# pc_healthypi_move_sensor_dual.net
KiCad netlist of a schematic drawn in EAGLE
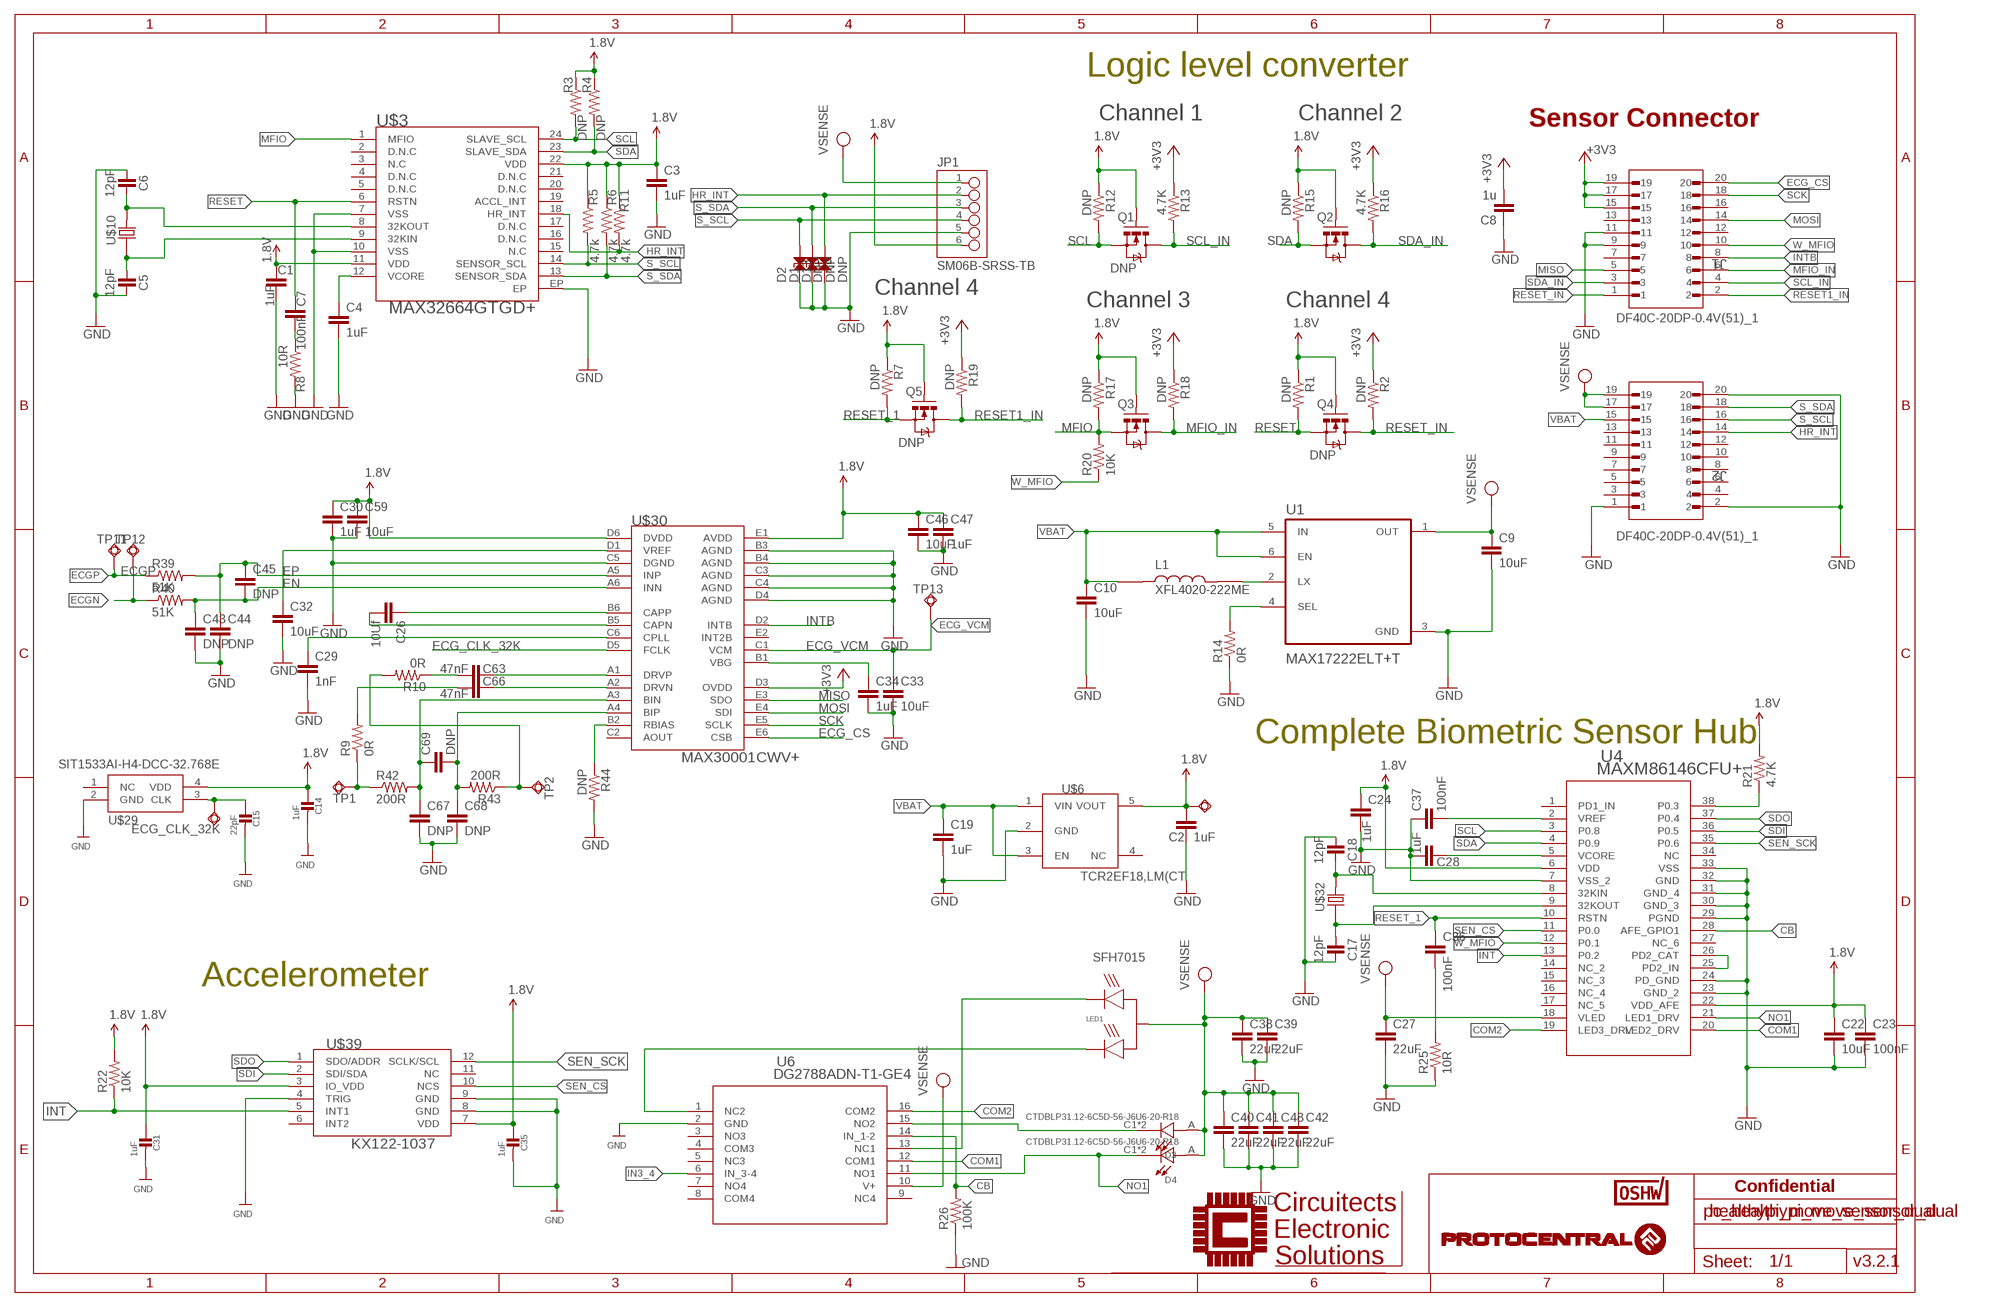
[diagram p0: schematic, sheet 1]

(export (version "E")
  (design (tool "Eeschema 10.0.6"))
  (components
    (comp (ref "C1")
      (value "1uF")
      (footprint "eagle-import:C0402")
      (libsource (lib "eagle-import") (part "C-EUC0402"))
    )
    (comp (ref "C2")
      (value "1uF")
      (footprint "eagle-import:C0402")
      (libsource (lib "eagle-import") (part "C-EUC0402"))
    )
    (comp (ref "C3")
      (value "1uF")
      (footprint "eagle-import:C0402")
      (libsource (lib "eagle-import") (part "C-EUC0402"))
    )
    (comp (ref "C4")
      (value "1uF")
      (footprint "eagle-import:C0402")
      (libsource (lib "eagle-import") (part "C-EUC0402"))
    )
    (comp (ref "C5")
      (value "12pF")
      (footprint "eagle-import:C0402")
      (libsource (lib "eagle-import") (part "CAPACITORS-0402"))
    )
    (comp (ref "C6")
      (value "12pF")
      (footprint "eagle-import:C0402")
      (libsource (lib "eagle-import") (part "CAPACITORS-0402"))
    )
    (comp (ref "C7")
      (value "100nF")
      (footprint "eagle-import:C0402")
      (libsource (lib "eagle-import") (part "C-EUC0402"))
    )
    (comp (ref "C8")
      (value "1u")
      (footprint "eagle-import:C0402")
      (libsource (lib "eagle-import") (part "C-EUC0402"))
    )
    (comp (ref "C9")
      (value "10uF")
      (footprint "eagle-import:C0402")
      (libsource (lib "eagle-import") (part "C-EUC0402"))
    )
    (comp (ref "C10")
      (value "10uF")
      (footprint "eagle-import:C0402")
      (libsource (lib "eagle-import") (part "C-EUC0402"))
    )
    (comp (ref "C14")
      (value "1uF")
      (footprint "eagle-import:0402")
      (libsource (lib "eagle-import") (part "CAP_CERAMIC0402"))
    )
    (comp (ref "C15")
      (value "22pF")
      (footprint "eagle-import:0402")
      (libsource (lib "eagle-import") (part "CAP_CERAMIC0402"))
    )
    (comp (ref "C17")
      (value "12pF")
      (footprint "eagle-import:C0402")
      (libsource (lib "eagle-import") (part "CAPACITORS-0402"))
    )
    (comp (ref "C18")
      (value "12pF")
      (footprint "eagle-import:C0402")
      (libsource (lib "eagle-import") (part "CAPACITORS-0402"))
    )
    (comp (ref "C19")
      (value "1uF")
      (footprint "eagle-import:C0402")
      (libsource (lib "eagle-import") (part "C-EUC0402"))
    )
    (comp (ref "C22")
      (value "10uF")
      (footprint "eagle-import:C0402")
      (libsource (lib "eagle-import") (part "C-EUC0402"))
    )
    (comp (ref "C23")
      (value "100nF")
      (footprint "eagle-import:C0402")
      (libsource (lib "eagle-import") (part "C-EUC0402"))
    )
    (comp (ref "C24")
      (value "1uF")
      (footprint "eagle-import:C0402")
      (libsource (lib "eagle-import") (part "C-EUC0402"))
    )
    (comp (ref "C26")
      (value "10Uf")
      (footprint "eagle-import:C0402")
      (libsource (lib "eagle-import") (part "C-EUC0402"))
    )
    (comp (ref "C27")
      (value "22uF")
      (footprint "eagle-import:C0805")
      (libsource (lib "eagle-import") (part "C-EUC0805"))
    )
    (comp (ref "C28")
      (value "1uF")
      (footprint "eagle-import:C0402")
      (libsource (lib "eagle-import") (part "C-EUC0402"))
    )
    (comp (ref "C29")
      (value "1nF")
      (footprint "eagle-import:C0402")
      (libsource (lib "eagle-import") (part "C-EUC0402"))
    )
    (comp (ref "C30")
      (value "1uF")
      (footprint "eagle-import:C0402")
      (libsource (lib "eagle-import") (part "C-EUC0402"))
    )
    (comp (ref "C31")
      (value "1uF")
      (footprint "eagle-import:0402")
      (libsource (lib "eagle-import") (part "CAP_CERAMIC0402"))
    )
    (comp (ref "C32")
      (value "10uF")
      (footprint "eagle-import:C0402")
      (libsource (lib "eagle-import") (part "C-EUC0402"))
    )
    (comp (ref "C33")
      (value "10uF")
      (footprint "eagle-import:C0402")
      (libsource (lib "eagle-import") (part "C-EUC0402"))
    )
    (comp (ref "C34")
      (value "1uF")
      (footprint "eagle-import:C0402")
      (libsource (lib "eagle-import") (part "C-EUC0402"))
    )
    (comp (ref "C35")
      (value "1uF")
      (footprint "eagle-import:0402")
      (libsource (lib "eagle-import") (part "CAP_CERAMIC0402"))
    )
    (comp (ref "C36")
      (value "100nF")
      (footprint "eagle-import:C0402")
      (libsource (lib "eagle-import") (part "C-EUC0402"))
    )
    (comp (ref "C37")
      (value "100nF")
      (footprint "eagle-import:C0402")
      (libsource (lib "eagle-import") (part "C-EUC0402"))
    )
    (comp (ref "C38")
      (value "22uF")
      (footprint "eagle-import:C0805")
      (libsource (lib "eagle-import") (part "C-EUC0805"))
    )
    (comp (ref "C39")
      (value "22uF")
      (footprint "eagle-import:C0805")
      (libsource (lib "eagle-import") (part "C-EUC0805"))
    )
    (comp (ref "C40")
      (value "22uF")
      (footprint "eagle-import:C0805")
      (libsource (lib "eagle-import") (part "C-EUC0805"))
    )
    (comp (ref "C41")
      (value "22uF")
      (footprint "eagle-import:C0805")
      (libsource (lib "eagle-import") (part "C-EUC0805"))
    )
    (comp (ref "C42")
      (value "22uF")
      (footprint "eagle-import:C0805")
      (libsource (lib "eagle-import") (part "C-EUC0805"))
    )
    (comp (ref "C43")
      (value "DNP")
      (footprint "eagle-import:C0402")
      (libsource (lib "eagle-import") (part "C-EUC0402"))
    )
    (comp (ref "C44")
      (value "DNP")
      (footprint "eagle-import:C0402")
      (libsource (lib "eagle-import") (part "C-EUC0402"))
    )
    (comp (ref "C45")
      (value "DNP")
      (footprint "eagle-import:C0402")
      (libsource (lib "eagle-import") (part "C-EUC0402"))
    )
    (comp (ref "C46")
      (value "10uF")
      (footprint "eagle-import:C0402")
      (libsource (lib "eagle-import") (part "C-EUC0402"))
    )
    (comp (ref "C47")
      (value "1uF")
      (footprint "eagle-import:C0402")
      (libsource (lib "eagle-import") (part "C-EUC0402"))
    )
    (comp (ref "C48")
      (value "22uF")
      (footprint "eagle-import:C0805")
      (libsource (lib "eagle-import") (part "C-EUC0805"))
    )
    (comp (ref "C59")
      (value "10uF")
      (footprint "eagle-import:C0402")
      (libsource (lib "eagle-import") (part "C-EUC0402"))
    )
    (comp (ref "C63")
      (value "47nF")
      (footprint "eagle-import:C0402")
      (libsource (lib "eagle-import") (part "C-EUC0402"))
    )
    (comp (ref "C66")
      (value "47nF")
      (footprint "eagle-import:C0402")
      (libsource (lib "eagle-import") (part "C-EUC0402"))
    )
    (comp (ref "C67")
      (value "DNP")
      (footprint "eagle-import:C0402")
      (libsource (lib "eagle-import") (part "C-EUC0402"))
    )
    (comp (ref "C68")
      (value "DNP")
      (footprint "eagle-import:C0402")
      (libsource (lib "eagle-import") (part "C-EUC0402"))
    )
    (comp (ref "C69")
      (value "DNP")
      (footprint "eagle-import:C0402")
      (libsource (lib "eagle-import") (part "C-EUC0402"))
    )
    (comp (ref "D1")
      (value "DNP")
      (footprint "eagle-import:0402")
      (fields
        (field (name "DIGIKEY_PART") "PESD0402-140CT-ND")
        (field (name "MOUSE_PART") "650-PESD0402-140")
      )
      (libsource (lib "eagle-import") (part "PESD0402-0402"))
    )
    (comp (ref "D2")
      (value "DNP")
      (footprint "eagle-import:0402")
      (fields
        (field (name "DIGIKEY_PART") "PESD0402-140CT-ND")
        (field (name "MOUSE_PART") "650-PESD0402-140")
      )
      (libsource (lib "eagle-import") (part "PESD0402-0402"))
    )
    (comp (ref "D3")
      (value "CTDBLP31.12-6C5D-56-J6U6-20-R18")
      (footprint "eagle-import:LED_CTDBLP31.12-6C5D-56-J6U6-20-R18")
      (fields
        (field (name "MF") "OSRAM Opto Semiconductors")
        (field (name "MP") "CT DBLP31.12-6C5D-56-J6U6-20-R18")
      )
      (libsource (lib "eagle-import") (part "CTDBLP31.12-6C5D-56-J6U6-20-R18"))
    )
    (comp (ref "D4")
      (value "CTDBLP31.12-6C5D-56-J6U6-20-R18")
      (footprint "eagle-import:LED_CTDBLP31.12-6C5D-56-J6U6-20-R18")
      (fields
        (field (name "MF") "OSRAM Opto Semiconductors")
        (field (name "MP") "CT DBLP31.12-6C5D-56-J6U6-20-R18")
      )
      (libsource (lib "eagle-import") (part "CTDBLP31.12-6C5D-56-J6U6-20-R18"))
    )
    (comp (ref "D13")
      (value "DNP")
      (footprint "eagle-import:0402")
      (fields
        (field (name "DIGIKEY_PART") "PESD0402-140CT-ND")
        (field (name "MOUSE_PART") "650-PESD0402-140")
      )
      (libsource (lib "eagle-import") (part "PESD0402-0402"))
    )
    (comp (ref "J1")
      (value "DF40C-20DP-0.4V(51)_1")
      (footprint "eagle-import:HRS_DF40C-20DP-0.4V(51)")
      (fields (field (name "MANUFACTURER") "Hirose Electric"))
      (libsource (lib "eagle-import") (part "DF40C-20DP-0.4V(51)_1"))
    )
    (comp (ref "J2")
      (value "DF40C-20DP-0.4V(51)_1")
      (footprint "eagle-import:HRS_DF40C-20DP-0.4V(51)")
      (fields (field (name "MANUFACTURER") "Hirose Electric"))
      (libsource (lib "eagle-import") (part "DF40C-20DP-0.4V(51)_1"))
    )
    (comp (ref "JP1")
      (value "SM06B-SRSS-TB")
      (footprint "eagle-import:SM06B-SRSS-TB")
      (fields (field (name "MF") "JST Sales"))
      (libsource (lib "eagle-import") (part "SM06B-SRSS-TB"))
    )
    (comp (ref "L1")
      (value "XFL4020-222ME")
      (footprint "eagle-import:IND_XFL4020-222ME")
      (fields (field (name "MF") "Coilcraft"))
      (libsource (lib "eagle-import") (part "XFL4020-222ME"))
    )
    (comp (ref "LED1")
      (value "SFH7015")
      (footprint "eagle-import:SFH7015")
      (fields (field (name "MF") "OSRAM Opto Semiconductors") (field (name "MP") "SFH 7015"))
      (libsource (lib "eagle-import") (part "SFH7015"))
    )
    (comp (ref "Q1")
      (value "DNP")
      (footprint "eagle-import:SOT23-3")
      (libsource (lib "eagle-import") (part "MOSFET-NCHANNELSMD"))
    )
    (comp (ref "Q2")
      (value "DNP")
      (footprint "eagle-import:SOT23-3")
      (libsource (lib "eagle-import") (part "MOSFET-NCHANNELSMD"))
    )
    (comp (ref "Q3")
      (value "DNP")
      (footprint "eagle-import:SOT23-3")
      (libsource (lib "eagle-import") (part "MOSFET-NCHANNELSMD"))
    )
    (comp (ref "Q4")
      (value "DNP")
      (footprint "eagle-import:SOT23-3")
      (libsource (lib "eagle-import") (part "MOSFET-NCHANNELSMD"))
    )
    (comp (ref "Q5")
      (value "DNP")
      (footprint "eagle-import:SOT23-3")
      (libsource (lib "eagle-import") (part "MOSFET-NCHANNELSMD"))
    )
    (comp (ref "R1")
      (value "DNP")
      (footprint "eagle-import:0402-RES")
      (libsource (lib "eagle-import") (part "RESISTOR0402-RES"))
    )
    (comp (ref "R2")
      (value "DNP")
      (footprint "eagle-import:0402-RES")
      (libsource (lib "eagle-import") (part "RESISTOR0402-RES"))
    )
    (comp (ref "R3")
      (value "DNP")
      (footprint "eagle-import:0402-RES")
      (libsource (lib "eagle-import") (part "RESISTOR0402-RES"))
    )
    (comp (ref "R4")
      (value "DNP")
      (footprint "eagle-import:0402-RES")
      (libsource (lib "eagle-import") (part "RESISTOR0402-RES"))
    )
    (comp (ref "R5")
      (value "4.7k")
      (footprint "eagle-import:0402-RES")
      (libsource (lib "eagle-import") (part "RESISTOR0402-RES"))
    )
    (comp (ref "R6")
      (value "4.7k")
      (footprint "eagle-import:0402-RES")
      (libsource (lib "eagle-import") (part "RESISTOR0402-RES"))
    )
    (comp (ref "R7")
      (value "DNP")
      (footprint "eagle-import:0402-RES")
      (libsource (lib "eagle-import") (part "RESISTOR0402-RES"))
    )
    (comp (ref "R8")
      (value "10R")
      (footprint "eagle-import:0402-RES")
      (libsource (lib "eagle-import") (part "RESISTOR0402-RES"))
    )
    (comp (ref "R9")
      (value "0R")
      (footprint "eagle-import:0402-RES")
      (libsource (lib "eagle-import") (part "RESISTOR0402-RES"))
    )
    (comp (ref "R10")
      (value "0R")
      (footprint "eagle-import:0402-RES")
      (libsource (lib "eagle-import") (part "RESISTOR0402-RES"))
    )
    (comp (ref "R11")
      (value "4.7k")
      (footprint "eagle-import:0402-RES")
      (libsource (lib "eagle-import") (part "RESISTOR0402-RES"))
    )
    (comp (ref "R12")
      (value "DNP")
      (footprint "eagle-import:0402-RES")
      (libsource (lib "eagle-import") (part "RESISTOR0402-RES"))
    )
    (comp (ref "R13")
      (value "4.7K")
      (footprint "eagle-import:0402-RES")
      (libsource (lib "eagle-import") (part "RESISTOR0402-RES"))
    )
    (comp (ref "R14")
      (value "0R")
      (footprint "eagle-import:R0402")
      (libsource (lib "eagle-import") (part "R-US_R0402"))
    )
    (comp (ref "R15")
      (value "DNP")
      (footprint "eagle-import:0402-RES")
      (libsource (lib "eagle-import") (part "RESISTOR0402-RES"))
    )
    (comp (ref "R16")
      (value "4.7K")
      (footprint "eagle-import:0402-RES")
      (libsource (lib "eagle-import") (part "RESISTOR0402-RES"))
    )
    (comp (ref "R17")
      (value "DNP")
      (footprint "eagle-import:0402-RES")
      (libsource (lib "eagle-import") (part "RESISTOR0402-RES"))
    )
    (comp (ref "R18")
      (value "DNP")
      (footprint "eagle-import:0402-RES")
      (libsource (lib "eagle-import") (part "RESISTOR0402-RES"))
    )
    (comp (ref "R19")
      (value "DNP")
      (footprint "eagle-import:0402-RES")
      (libsource (lib "eagle-import") (part "RESISTOR0402-RES"))
    )
    (comp (ref "R20")
      (value "10K")
      (footprint "eagle-import:0402-RES")
      (libsource (lib "eagle-import") (part "RESISTOR0402-RES"))
    )
    (comp (ref "R21")
      (value "4.7K")
      (footprint "eagle-import:R0402")
      (libsource (lib "eagle-import") (part "R-US_R0402"))
    )
    (comp (ref "R22")
      (value "10K")
      (footprint "eagle-import:0402-RES")
      (libsource (lib "eagle-import") (part "RESISTOR0402-RES"))
    )
    (comp (ref "R25")
      (value "10R")
      (footprint "eagle-import:R0402")
      (libsource (lib "eagle-import") (part "R-US_R0402"))
    )
    (comp (ref "R26")
      (value "100K")
      (footprint "eagle-import:R0402")
      (libsource (lib "eagle-import") (part "R-US_R0402"))
    )
    (comp (ref "R39")
      (value "51K")
      (footprint "eagle-import:0402-RES")
      (libsource (lib "eagle-import") (part "RESISTOR0402-RES"))
    )
    (comp (ref "R40")
      (value "51K")
      (footprint "eagle-import:0402-RES")
      (libsource (lib "eagle-import") (part "RESISTOR0402-RES"))
    )
    (comp (ref "R42")
      (value "200R")
      (footprint "eagle-import:0402-RES")
      (libsource (lib "eagle-import") (part "RESISTOR0402-RES"))
    )
    (comp (ref "R43")
      (value "200R")
      (footprint "eagle-import:0402-RES")
      (libsource (lib "eagle-import") (part "RESISTOR0402-RES"))
    )
    (comp (ref "R44")
      (value "DNP")
      (footprint "eagle-import:0402-RES")
      (libsource (lib "eagle-import") (part "RESISTOR0402-RES"))
    )
    (comp (ref "SWIO1")
      (value "TPSQTP11R")
      (footprint "eagle-import:TP11R")
      (libsource (lib "eagle-import") (part "TPSQTP11R"))
    )
    (comp (ref "SWIO5")
      (value "TPSQTP11R")
      (footprint "eagle-import:TP11R")
      (libsource (lib "eagle-import") (part "TPSQTP11R"))
    )
    (comp (ref "TP1")
      (value "TPSQTP20SQ")
      (footprint "eagle-import:TP20SQ")
      (libsource (lib "eagle-import") (part "TPSQTP20SQ"))
    )
    (comp (ref "TP2")
      (value "TPSQTP20SQ")
      (footprint "eagle-import:TP20SQ")
      (libsource (lib "eagle-import") (part "TPSQTP20SQ"))
    )
    (comp (ref "TP11")
      (value "TPSQTP20SQ")
      (footprint "eagle-import:TP20SQ")
      (libsource (lib "eagle-import") (part "TPSQTP20SQ"))
    )
    (comp (ref "TP12")
      (value "TPSQTP20SQ")
      (footprint "eagle-import:TP20SQ")
      (libsource (lib "eagle-import") (part "TPSQTP20SQ"))
    )
    (comp (ref "TP13")
      (value "TPSQTP20SQ")
      (footprint "eagle-import:TP20SQ")
      (libsource (lib "eagle-import") (part "TPSQTP20SQ"))
    )
    (comp (ref "U$3")
      (value "MAX32664GTGD+")
      (footprint "eagle-import:TQFN-24L")
      (libsource (lib "eagle-import") (part "MAX32664GTGA+"))
    )
    (comp (ref "U$6")
      (value "TCR2EF18,LM(CT")
      (footprint "eagle-import:SOT95P285X140-5N")
      (libsource (lib "eagle-import") (part "AP7354D-18W5-7"))
    )
    (comp (ref "U$10")
      (value "520-327-12.5-34B(32.768KHZ)")
      (footprint "eagle-import:ECX-31B")
      (libsource (lib "eagle-import") (part "ECS-X-34B"))
    )
    (comp (ref "U$29")
      (value "SIT1533AI-H4-DCC-32.768E")
      (footprint "eagle-import:SIT1533")
      (libsource (lib "eagle-import") (part "SIT1533AI-H4-DCC-32.768E"))
    )
    (comp (ref "U$30")
      (value "MAX30001CWV+")
      (footprint "eagle-import:30WLP")
      (libsource (lib "eagle-import") (part "MAX30001CWV+"))
    )
    (comp (ref "U$32")
      (value "520-327-12.5-34B(32.768KHZ)")
      (footprint "eagle-import:ECX-31B")
      (libsource (lib "eagle-import") (part "ECS-X-34B"))
    )
    (comp (ref "U$39")
      (value "KX122-1037")
      (footprint "eagle-import:KIONIX_KXTJ3-1057")
      (libsource (lib "eagle-import") (part "KX122-1037"))
    )
    (comp (ref "U$48")
      (value "CERT-SMALL")
      (footprint "eagle-import:CERT-SMALL-SILK")
      (libsource (lib "eagle-import") (part "CERT-SMALL"))
    )
    (comp (ref "U1")
      (value "MAX17222ELT+T")
      (footprint "eagle-import:SON65P200X200X80-6N")
      (fields (field (name "MF") "Analog Devices"))
      (libsource (lib "eagle-import") (part "MAX17222ELT+T"))
    )
    (comp (ref "U4")
      (value "MAXM86146CFU+")
      (footprint "eagle-import:21-100323A_90-100112A_MXM")
      (fields (field (name "COPYRIGHT") "Copyright (C) 2023 Ultra Librarian. All rights reserved."))
      (libsource (lib "eagle-import") (part "MAXM86146CFU+"))
    )
    (comp (ref "U6")
      (value "DG2788ADN-T1-GE4")
      (footprint "eagle-import:MINIQFN-16_VIS")
      (fields (field (name "COPYRIGHT") "Copyright (C) 2023 Ultra Librarian. All rights reserved."))
      (libsource (lib "eagle-import") (part "DG2788ADN-T1-GE4"))
    )
  )
  (nets
    (net (code "1") (name "+3V3") (class "Default")
      (node (ref "C8") (pin "2") (pinfunction "2_2") (pintype "passive"))
      (node (ref "J1") (pin "15") (pinfunction "15_15") (pintype "passive"))
      (node (ref "J1") (pin "17") (pinfunction "17_17") (pintype "passive"))
      (node (ref "J1") (pin "19") (pinfunction "19_19") (pintype "passive"))
      (node (ref "R13") (pin "1") (pinfunction "1_1") (pintype "passive"))
      (node (ref "R16") (pin "1") (pinfunction "1_1") (pintype "passive"))
      (node (ref "R18") (pin "1") (pinfunction "1_1") (pintype "passive"))
      (node (ref "R19") (pin "1") (pinfunction "1_1") (pintype "passive"))
      (node (ref "R2") (pin "1") (pinfunction "1_1") (pintype "passive"))
      (node (ref "U$30") (pin "D3") (pinfunction "OVDD_D3") (pintype "bidirectional"))
    )
    (net (code "2") (name "/ECG_CLK_32K") (class "Default")
      (node (ref "C15") (pin "1") (pinfunction "P$1_1") (pintype "passive"))
      (node (ref "SWIO1") (pin "TP") (pinfunction "TP_TP") (pintype "input"))
      (node (ref "U$29") (pin "3") (pinfunction "CLK_3") (pintype "bidirectional"))
      (node (ref "U$30") (pin "D5") (pinfunction "FCLK_D5") (pintype "bidirectional"))
    )
    (net (code "3") (name "/EN") (class "Default")
      (node (ref "C43") (pin "1") (pinfunction "1_1") (pintype "passive"))
      (node (ref "C45") (pin "2") (pinfunction "2_2") (pintype "passive"))
      (node (ref "R40") (pin "2") (pinfunction "2_2") (pintype "passive"))
      (node (ref "U$30") (pin "A6") (pinfunction "INN_A6") (pintype "bidirectional"))
    )
    (net (code "4") (name "/EP") (class "Default")
      (node (ref "C44") (pin "1") (pinfunction "1_1") (pintype "passive"))
      (node (ref "C45") (pin "1") (pinfunction "1_1") (pintype "passive"))
      (node (ref "R39") (pin "2") (pinfunction "2_2") (pintype "passive"))
      (node (ref "U$30") (pin "A5") (pinfunction "INP_A5") (pintype "bidirectional"))
    )
    (net (code "5") (name "1.8V") (class "Default")
      (node (ref "C1") (pin "1") (pinfunction "1_1") (pintype "passive"))
      (node (ref "C14") (pin "1") (pinfunction "P$1_1") (pintype "passive"))
      (node (ref "C2") (pin "1") (pinfunction "1_1") (pintype "passive"))
      (node (ref "C22") (pin "1") (pinfunction "1_1") (pintype "passive"))
      (node (ref "C23") (pin "1") (pinfunction "1_1") (pintype "passive"))
      (node (ref "C24") (pin "1") (pinfunction "1_1") (pintype "passive"))
      (node (ref "C3") (pin "1") (pinfunction "1_1") (pintype "passive"))
      (node (ref "C30") (pin "1") (pinfunction "1_1") (pintype "passive"))
      (node (ref "C31") (pin "1") (pinfunction "P$1_1") (pintype "passive"))
      (node (ref "C35") (pin "1") (pinfunction "P$1_1") (pintype "passive"))
      (node (ref "C46") (pin "1") (pinfunction "1_1") (pintype "passive"))
      (node (ref "C47") (pin "1") (pinfunction "1_1") (pintype "passive"))
      (node (ref "C59") (pin "1") (pinfunction "1_1") (pintype "passive"))
      (node (ref "JP1") (pin "6") (pinfunction "P$6_6") (pintype "bidirectional"))
      (node (ref "Q1") (pin "1") (pinfunction "G_1") (pintype "passive"))
      (node (ref "Q2") (pin "1") (pinfunction "G_1") (pintype "passive"))
      (node (ref "Q3") (pin "1") (pinfunction "G_1") (pintype "passive"))
      (node (ref "Q4") (pin "1") (pinfunction "G_1") (pintype "passive"))
      (node (ref "Q5") (pin "1") (pinfunction "G_1") (pintype "passive"))
      (node (ref "R1") (pin "1") (pinfunction "1_1") (pintype "passive"))
      (node (ref "R11") (pin "1") (pinfunction "1_1") (pintype "passive"))
      (node (ref "R12") (pin "1") (pinfunction "1_1") (pintype "passive"))
      (node (ref "R15") (pin "1") (pinfunction "1_1") (pintype "passive"))
      (node (ref "R17") (pin "1") (pinfunction "1_1") (pintype "passive"))
      (node (ref "R21") (pin "2") (pinfunction "2_2") (pintype "passive"))
      (node (ref "R22") (pin "2") (pinfunction "2_2") (pintype "passive"))
      (node (ref "R3") (pin "1") (pinfunction "1_1") (pintype "passive"))
      (node (ref "R4") (pin "1") (pinfunction "1_1") (pintype "passive"))
      (node (ref "R5") (pin "1") (pinfunction "1_1") (pintype "passive"))
      (node (ref "R6") (pin "1") (pinfunction "1_1") (pintype "passive"))
      (node (ref "R7") (pin "1") (pinfunction "1_1") (pintype "passive"))
      (node (ref "SWIO5") (pin "TP") (pinfunction "TP_TP") (pintype "input"))
      (node (ref "U$29") (pin "4") (pinfunction "VDD_4") (pintype "bidirectional"))
      (node (ref "U$3") (pin "11") (pinfunction "VDD_11") (pintype "bidirectional"))
      (node (ref "U$3") (pin "22") (pinfunction "VDD_22") (pintype "bidirectional"))
      (node (ref "U$30") (pin "D6") (pinfunction "DVDD_D6") (pintype "bidirectional"))
      (node (ref "U$30") (pin "E1") (pinfunction "AVDD_E1") (pintype "bidirectional"))
      (node (ref "U$39") (pin "3") (pinfunction "IO_VDD_3") (pintype "bidirectional"))
      (node (ref "U$39") (pin "7") (pinfunction "VDD_7") (pintype "bidirectional"))
      (node (ref "U$6") (pin "5") (pinfunction "VOUT_5") (pintype "bidirectional"))
      (node (ref "U4") (pin "22") (pinfunction "VDD_AFE_22") (pintype "input"))
      (node (ref "U4") (pin "6") (pinfunction "VDD_6") (pintype "power_in"))
    )
    (net (code "6") (name "CB") (class "Default")
      (node (ref "R26") (pin "2") (pinfunction "2_2") (pintype "passive"))
      (node (ref "U4") (pin "28") (pinfunction "AFE_GPIO1_28") (pintype "bidirectional"))
      (node (ref "U6") (pin "14") (pinfunction "IN_1-2_14") (pintype "bidirectional"))
    )
    (net (code "7") (name "COM1") (class "Default")
      (node (ref "U4") (pin "20") (pinfunction "LED2_DRV_20") (pintype "output"))
      (node (ref "U6") (pin "12") (pinfunction "COM1_12") (pintype "bidirectional"))
    )
    (net (code "8") (name "COM2") (class "Default")
      (node (ref "U4") (pin "19") (pinfunction "LED3_DRV_19") (pintype "output"))
      (node (ref "U6") (pin "16") (pinfunction "COM2_16") (pintype "bidirectional"))
    )
    (net (code "9") (name "ECGN") (class "Default")
      (node (ref "R40") (pin "1") (pinfunction "1_1") (pintype "passive"))
      (node (ref "TP12") (pin "TP") (pinfunction "TP_TP") (pintype "input"))
    )
    (net (code "10") (name "ECGP") (class "Default")
      (node (ref "R39") (pin "1") (pinfunction "1_1") (pintype "passive"))
      (node (ref "TP11") (pin "TP") (pinfunction "TP_TP") (pintype "input"))
    )
    (net (code "11") (name "ECG_CS") (class "Default")
      (node (ref "J1") (pin "20") (pinfunction "20_20") (pintype "passive"))
      (node (ref "U$30") (pin "E6") (pinfunction "CSB_E6") (pintype "bidirectional"))
    )
    (net (code "12") (name "ECG_VCM") (class "Default")
      (node (ref "C33") (pin "1") (pinfunction "1_1") (pintype "passive"))
      (node (ref "TP13") (pin "TP") (pinfunction "TP_TP") (pintype "input"))
      (node (ref "U$30") (pin "C1") (pinfunction "VCM_C1") (pintype "bidirectional"))
    )
    (net (code "13") (name "GND") (class "Default")
      (node (ref "C1") (pin "2") (pinfunction "2_2") (pintype "passive"))
      (node (ref "C10") (pin "2") (pinfunction "2_2") (pintype "passive"))
      (node (ref "C14") (pin "2") (pinfunction "P$2_2") (pintype "passive"))
      (node (ref "C15") (pin "2") (pinfunction "P$2_2") (pintype "passive"))
      (node (ref "C17") (pin "2") (pinfunction "2_2") (pintype "passive"))
      (node (ref "C18") (pin "1") (pinfunction "1_1") (pintype "passive"))
      (node (ref "C19") (pin "2") (pinfunction "2_2") (pintype "passive"))
      (node (ref "C2") (pin "2") (pinfunction "2_2") (pintype "passive"))
      (node (ref "C22") (pin "2") (pinfunction "2_2") (pintype "passive"))
      (node (ref "C23") (pin "2") (pinfunction "2_2") (pintype "passive"))
      (node (ref "C24") (pin "2") (pinfunction "2_2") (pintype "passive"))
      (node (ref "C27") (pin "2") (pinfunction "2_2") (pintype "passive"))
      (node (ref "C28") (pin "2") (pinfunction "2_2") (pintype "passive"))
      (node (ref "C29") (pin "2") (pinfunction "2_2") (pintype "passive"))
      (node (ref "C3") (pin "2") (pinfunction "2_2") (pintype "passive"))
      (node (ref "C30") (pin "2") (pinfunction "2_2") (pintype "passive"))
      (node (ref "C31") (pin "2") (pinfunction "P$2_2") (pintype "passive"))
      (node (ref "C32") (pin "2") (pinfunction "2_2") (pintype "passive"))
      (node (ref "C33") (pin "2") (pinfunction "2_2") (pintype "passive"))
      (node (ref "C34") (pin "2") (pinfunction "2_2") (pintype "passive"))
      (node (ref "C35") (pin "2") (pinfunction "P$2_2") (pintype "passive"))
      (node (ref "C37") (pin "1") (pinfunction "1_1") (pintype "passive"))
      (node (ref "C38") (pin "2") (pinfunction "2_2") (pintype "passive"))
      (node (ref "C39") (pin "2") (pinfunction "2_2") (pintype "passive"))
      (node (ref "C4") (pin "2") (pinfunction "2_2") (pintype "passive"))
      (node (ref "C40") (pin "2") (pinfunction "2_2") (pintype "passive"))
      (node (ref "C41") (pin "2") (pinfunction "2_2") (pintype "passive"))
      (node (ref "C42") (pin "2") (pinfunction "2_2") (pintype "passive"))
      (node (ref "C43") (pin "2") (pinfunction "2_2") (pintype "passive"))
      (node (ref "C44") (pin "2") (pinfunction "2_2") (pintype "passive"))
      (node (ref "C46") (pin "2") (pinfunction "2_2") (pintype "passive"))
      (node (ref "C47") (pin "2") (pinfunction "2_2") (pintype "passive"))
      (node (ref "C48") (pin "2") (pinfunction "2_2") (pintype "passive"))
      (node (ref "C5") (pin "2") (pinfunction "2_2") (pintype "passive"))
      (node (ref "C59") (pin "2") (pinfunction "2_2") (pintype "passive"))
      (node (ref "C6") (pin "1") (pinfunction "1_1") (pintype "passive"))
      (node (ref "C67") (pin "2") (pinfunction "2_2") (pintype "passive"))
      (node (ref "C68") (pin "2") (pinfunction "2_2") (pintype "passive"))
      (node (ref "C8") (pin "1") (pinfunction "1_1") (pintype "passive"))
      (node (ref "C9") (pin "2") (pinfunction "2_2") (pintype "passive"))
      (node (ref "D1") (pin "1") (pinfunction "1_1") (pintype "bidirectional"))
      (node (ref "D13") (pin "1") (pinfunction "1_1") (pintype "bidirectional"))
      (node (ref "D2") (pin "1") (pinfunction "1_1") (pintype "bidirectional"))
      (node (ref "J1") (pin "11") (pinfunction "11_11") (pintype "passive"))
      (node (ref "J1") (pin "9") (pinfunction "9_9") (pintype "passive"))
      (node (ref "J2") (pin "1") (pinfunction "1_1") (pintype "passive"))
      (node (ref "J2") (pin "2") (pinfunction "2_2") (pintype "passive"))
      (node (ref "J2") (pin "20") (pinfunction "20_20") (pintype "passive"))
      (node (ref "JP1") (pin "5") (pinfunction "P$5_5") (pintype "bidirectional"))
      (node (ref "R14") (pin "1") (pinfunction "1_1") (pintype "passive"))
      (node (ref "R25") (pin "1") (pinfunction "1_1") (pintype "passive"))
      (node (ref "R26") (pin "1") (pinfunction "1_1") (pintype "passive"))
      (node (ref "R44") (pin "2") (pinfunction "2_2") (pintype "passive"))
      (node (ref "R8") (pin "2") (pinfunction "2_2") (pintype "passive"))
      (node (ref "U$29") (pin "2") (pinfunction "GND_2") (pintype "bidirectional"))
      (node (ref "U$3") (pin "10") (pinfunction "VSS_10") (pintype "bidirectional"))
      (node (ref "U$3") (pin "7") (pinfunction "VSS_7") (pintype "bidirectional"))
      (node (ref "U$3") (pin "EP") (pinfunction "EP_EP") (pintype "bidirectional"))
      (node (ref "U$30") (pin "B3") (pinfunction "AGND_B3") (pintype "bidirectional"))
      (node (ref "U$30") (pin "B4") (pinfunction "AGND_B4") (pintype "bidirectional"))
      (node (ref "U$30") (pin "C3") (pinfunction "AGND_C3") (pintype "bidirectional"))
      (node (ref "U$30") (pin "C4") (pinfunction "AGND_C4") (pintype "bidirectional"))
      (node (ref "U$30") (pin "C5") (pinfunction "DGND_C5") (pintype "bidirectional"))
      (node (ref "U$30") (pin "D4") (pinfunction "AGND_D4") (pintype "bidirectional"))
      (node (ref "U$39") (pin "4") (pinfunction "TRIG_4") (pintype "bidirectional"))
      (node (ref "U$39") (pin "8") (pinfunction "GND_8") (pintype "bidirectional"))
      (node (ref "U$39") (pin "9") (pinfunction "GND_9") (pintype "bidirectional"))
      (node (ref "U$6") (pin "2") (pinfunction "GND_2") (pintype "bidirectional"))
      (node (ref "U1") (pin "3") (pinfunction "GND_3") (pintype "power_in"))
      (node (ref "U4") (pin "23") (pinfunction "GND_2_23") (pintype "power_in"))
      (node (ref "U4") (pin "24") (pinfunction "PD_GND_24") (pintype "passive"))
      (node (ref "U4") (pin "29") (pinfunction "PGND_29") (pintype "power_in"))
      (node (ref "U4") (pin "30") (pinfunction "GND_3_30") (pintype "power_in"))
      (node (ref "U4") (pin "31") (pinfunction "GND_4_31") (pintype "power_in"))
      (node (ref "U4") (pin "32") (pinfunction "GND_32") (pintype "power_in"))
      (node (ref "U4") (pin "33") (pinfunction "VSS_33") (pintype "power_in"))
      (node (ref "U4") (pin "7") (pinfunction "VSS_2_7") (pintype "power_in"))
      (node (ref "U6") (pin "2") (pinfunction "GND_2") (pintype "passive"))
    )
    (net (code "14") (name "HR_INT") (class "Default")
      (node (ref "D13") (pin "2") (pinfunction "2_2") (pintype "bidirectional"))
      (node (ref "J2") (pin "14") (pinfunction "14_14") (pintype "passive"))
      (node (ref "JP1") (pin "2") (pinfunction "P$2_2") (pintype "bidirectional"))
      (node (ref "R11") (pin "2") (pinfunction "2_2") (pintype "passive"))
      (node (ref "U$3") (pin "18") (pinfunction "HR_INT_18") (pintype "bidirectional"))
    )
    (net (code "15") (name "IN3_4") (class "Default")
      (node (ref "U6") (pin "6") (pinfunction "IN_3-4_6") (pintype "bidirectional"))
    )
    (net (code "16") (name "INT") (class "Default")
      (node (ref "R22") (pin "1") (pinfunction "1_1") (pintype "passive"))
      (node (ref "U$39") (pin "5") (pinfunction "INT1_5") (pintype "bidirectional"))
      (node (ref "U4") (pin "13") (pinfunction "P0.2_13") (pintype "passive"))
    )
    (net (code "17") (name "INTB") (class "Default")
      (node (ref "J1") (pin "8") (pinfunction "8_8") (pintype "passive"))
      (node (ref "U$30") (pin "D2") (pinfunction "INTB_D2") (pintype "bidirectional"))
    )
    (net (code "18") (name "MFIO") (class "Default")
      (node (ref "Q3") (pin "2") (pinfunction "S_2") (pintype "passive"))
      (node (ref "R17") (pin "2") (pinfunction "2_2") (pintype "passive"))
      (node (ref "R20") (pin "2") (pinfunction "2_2") (pintype "passive"))
      (node (ref "U$3") (pin "1") (pinfunction "MFIO_1") (pintype "bidirectional"))
    )
    (net (code "19") (name "MFIO_IN") (class "Default")
      (node (ref "J1") (pin "6") (pinfunction "6_6") (pintype "passive"))
      (node (ref "Q3") (pin "3") (pinfunction "D_3") (pintype "passive"))
      (node (ref "R18") (pin "2") (pinfunction "2_2") (pintype "passive"))
    )
    (net (code "20") (name "MISO") (class "Default")
      (node (ref "J1") (pin "5") (pinfunction "5_5") (pintype "passive"))
      (node (ref "U$30") (pin "E3") (pinfunction "SDO_E3") (pintype "bidirectional"))
    )
    (net (code "21") (name "MOSI") (class "Default")
      (node (ref "J1") (pin "14") (pinfunction "14_14") (pintype "passive"))
      (node (ref "U$30") (pin "E4") (pinfunction "SDI_E4") (pintype "bidirectional"))
    )
    (net (code "22") (name "NO1") (class "Default")
      (node (ref "D4") (pin "C1") (pinfunction "C_C1") (pintype "passive"))
      (node (ref "D4") (pin "C2") (pinfunction "C_C2") (pintype "passive"))
      (node (ref "U4") (pin "21") (pinfunction "LED1_DRV_21") (pintype "output"))
      (node (ref "U6") (pin "11") (pinfunction "NO1_11") (pintype "bidirectional"))
    )
    (net (code "23") (name "Net-(C7-Pad2)") (class "Default")
      (node (ref "C7") (pin "2") (pinfunction "2_2") (pintype "passive"))
      (node (ref "R8") (pin "1") (pinfunction "1_1") (pintype "passive"))
    )
    (net (code "24") (name "Net-(C36-Pad2)") (class "Default")
      (node (ref "C36") (pin "2") (pinfunction "2_2") (pintype "passive"))
      (node (ref "R25") (pin "2") (pinfunction "2_2") (pintype "passive"))
    )
    (net (code "25") (name "Net-(C63-Pad1)") (class "Default")
      (node (ref "C63") (pin "1") (pinfunction "1_1") (pintype "passive"))
      (node (ref "R10") (pin "1") (pinfunction "1_1") (pintype "passive"))
    )
    (net (code "26") (name "Net-(C66-Pad1)") (class "Default")
      (node (ref "C66") (pin "1") (pinfunction "1_1") (pintype "passive"))
      (node (ref "R9") (pin "2") (pinfunction "2_2") (pintype "passive"))
    )
    (net (code "27") (name "Net-(LED1-IRC)") (class "Default")
      (node (ref "LED1") (pin "4") (pinfunction "IRC_4") (pintype "passive"))
      (node (ref "U6") (pin "13") (pinfunction "NC1_13") (pintype "bidirectional"))
    )
    (net (code "28") (name "Net-(LED1-RC)") (class "Default")
      (node (ref "LED1") (pin "2") (pinfunction "RC_2") (pintype "passive"))
      (node (ref "U6") (pin "1") (pinfunction "NC2_1") (pintype "bidirectional"))
    )
    (net (code "29") (name "Net-(R10-Pad2)") (class "Default")
      (node (ref "R10") (pin "2") (pinfunction "2_2") (pintype "passive"))
      (node (ref "R43") (pin "1") (pinfunction "1_1") (pintype "passive"))
      (node (ref "TP2") (pin "TP") (pinfunction "TP_TP") (pintype "input"))
    )
    (net (code "30") (name "Net-(R42-Pad1)") (class "Default")
      (node (ref "R42") (pin "1") (pinfunction "1_1") (pintype "passive"))
      (node (ref "R9") (pin "1") (pinfunction "1_1") (pintype "passive"))
      (node (ref "TP1") (pin "TP") (pinfunction "TP_TP") (pintype "input"))
    )
    (net (code "31") (name "Net-(U$3-VCORE)") (class "Default")
      (node (ref "C4") (pin "1") (pinfunction "1_1") (pintype "passive"))
      (node (ref "U$3") (pin "12") (pinfunction "VCORE_12") (pintype "bidirectional"))
    )
    (net (code "32") (name "Net-(U$10-1)") (class "Default")
      (node (ref "C5") (pin "1") (pinfunction "1_1") (pintype "passive"))
      (node (ref "U$10") (pin "P$1") (pinfunction "1_P$1") (pintype "passive"))
      (node (ref "U$3") (pin "9") (pinfunction "32KIN_9") (pintype "bidirectional"))
    )
    (net (code "33") (name "Net-(U$10-2)") (class "Default")
      (node (ref "C6") (pin "2") (pinfunction "2_2") (pintype "passive"))
      (node (ref "U$10") (pin "P$2") (pinfunction "2_P$2") (pintype "passive"))
      (node (ref "U$3") (pin "8") (pinfunction "32KOUT_8") (pintype "bidirectional"))
    )
    (net (code "34") (name "Net-(U$30-BIN)") (class "Default")
      (node (ref "C67") (pin "1") (pinfunction "1_1") (pintype "passive"))
      (node (ref "C69") (pin "1") (pinfunction "1_1") (pintype "passive"))
      (node (ref "R42") (pin "2") (pinfunction "2_2") (pintype "passive"))
      (node (ref "U$30") (pin "A3") (pinfunction "BIN_A3") (pintype "bidirectional"))
    )
    (net (code "35") (name "Net-(U$30-BIP)") (class "Default")
      (node (ref "C68") (pin "1") (pinfunction "1_1") (pintype "passive"))
      (node (ref "C69") (pin "2") (pinfunction "2_2") (pintype "passive"))
      (node (ref "R43") (pin "2") (pinfunction "2_2") (pintype "passive"))
      (node (ref "U$30") (pin "A4") (pinfunction "BIP_A4") (pintype "bidirectional"))
    )
    (net (code "36") (name "Net-(U$30-CAPN)") (class "Default")
      (node (ref "C26") (pin "2") (pinfunction "2_2") (pintype "passive"))
      (node (ref "U$30") (pin "B5") (pinfunction "CAPN_B5") (pintype "bidirectional"))
    )
    (net (code "37") (name "Net-(U$30-CAPP)") (class "Default")
      (node (ref "C26") (pin "1") (pinfunction "1_1") (pintype "passive"))
      (node (ref "U$30") (pin "B6") (pinfunction "CAPP_B6") (pintype "bidirectional"))
    )
    (net (code "38") (name "Net-(U$30-CPLL)") (class "Default")
      (node (ref "C29") (pin "1") (pinfunction "1_1") (pintype "passive"))
      (node (ref "U$30") (pin "C6") (pinfunction "CPLL_C6") (pintype "bidirectional"))
    )
    (net (code "39") (name "Net-(U$30-DRVN)") (class "Default")
      (node (ref "C66") (pin "2") (pinfunction "2_2") (pintype "passive"))
      (node (ref "U$30") (pin "A2") (pinfunction "DRVN_A2") (pintype "bidirectional"))
    )
    (net (code "40") (name "Net-(U$30-DRVP)") (class "Default")
      (node (ref "C63") (pin "2") (pinfunction "2_2") (pintype "passive"))
      (node (ref "U$30") (pin "A1") (pinfunction "DRVP_A1") (pintype "bidirectional"))
    )
    (net (code "41") (name "Net-(U$30-RBIAS)") (class "Default")
      (node (ref "R44") (pin "1") (pinfunction "1_1") (pintype "passive"))
      (node (ref "U$30") (pin "B2") (pinfunction "RBIAS_B2") (pintype "bidirectional"))
    )
    (net (code "42") (name "Net-(U$30-VBG)") (class "Default")
      (node (ref "C34") (pin "1") (pinfunction "1_1") (pintype "passive"))
      (node (ref "U$30") (pin "B1") (pinfunction "VBG_B1") (pintype "bidirectional"))
    )
    (net (code "43") (name "Net-(U$30-VREF)") (class "Default")
      (node (ref "C32") (pin "1") (pinfunction "1_1") (pintype "passive"))
      (node (ref "U$30") (pin "D1") (pinfunction "VREF_D1") (pintype "bidirectional"))
    )
    (net (code "44") (name "Net-(U$32-1)") (class "Default")
      (node (ref "C17") (pin "1") (pinfunction "1_1") (pintype "passive"))
      (node (ref "U$32") (pin "P$1") (pinfunction "1_P$1") (pintype "passive"))
      (node (ref "U4") (pin "9") (pinfunction "32KOUT_9") (pintype "output"))
    )
    (net (code "45") (name "Net-(U$32-2)") (class "Default")
      (node (ref "C18") (pin "2") (pinfunction "2_2") (pintype "passive"))
      (node (ref "U$32") (pin "P$2") (pinfunction "2_P$2") (pintype "passive"))
      (node (ref "U4") (pin "8") (pinfunction "32KIN_8") (pintype "input"))
    )
    (net (code "46") (name "Net-(U1-LX)") (class "Default")
      (node (ref "L1") (pin "2") (pinfunction "2_2") (pintype "passive"))
      (node (ref "U1") (pin "2") (pinfunction "LX_2") (pintype "bidirectional"))
    )
    (net (code "47") (name "Net-(U1-SEL)") (class "Default")
      (node (ref "R14") (pin "2") (pinfunction "2_2") (pintype "passive"))
      (node (ref "U1") (pin "4") (pinfunction "SEL_4") (pintype "bidirectional"))
    )
    (net (code "48") (name "Net-(U4-P0.3)") (class "Default")
      (node (ref "R21") (pin "1") (pinfunction "1_1") (pintype "passive"))
      (node (ref "U4") (pin "38") (pinfunction "P0.3_38") (pintype "input"))
    )
    (net (code "49") (name "Net-(U4-PD2_CAT)") (class "Default")
      (node (ref "U4") (pin "25") (pinfunction "PD2_IN_25") (pintype "input"))
      (node (ref "U4") (pin "26") (pinfunction "PD2_CAT_26") (pintype "passive"))
    )
    (net (code "50") (name "Net-(U4-VCORE)") (class "Default")
      (node (ref "C28") (pin "1") (pinfunction "1_1") (pintype "passive"))
      (node (ref "U4") (pin "5") (pinfunction "VCORE_5") (pintype "power_in"))
    )
    (net (code "51") (name "Net-(U4-VREF)") (class "Default")
      (node (ref "C37") (pin "2") (pinfunction "2_2") (pintype "passive"))
      (node (ref "U4") (pin "2") (pinfunction "VREF_2") (pintype "passive"))
    )
    (net (code "52") (name "Net-(U6-NO2)") (class "Default")
      (node (ref "D3") (pin "C1") (pinfunction "C_C1") (pintype "passive"))
      (node (ref "D3") (pin "C2") (pinfunction "C_C2") (pintype "passive"))
      (node (ref "U6") (pin "15") (pinfunction "NO2_15") (pintype "bidirectional"))
    )
    (net (code "53") (name "RESET") (class "Default")
      (node (ref "C7") (pin "1") (pinfunction "1_1") (pintype "passive"))
      (node (ref "Q4") (pin "2") (pinfunction "S_2") (pintype "passive"))
      (node (ref "R1") (pin "2") (pinfunction "2_2") (pintype "passive"))
      (node (ref "U$3") (pin "6") (pinfunction "RSTN_6") (pintype "bidirectional"))
    )
    (net (code "54") (name "RESET1_IN") (class "Default")
      (node (ref "J1") (pin "2") (pinfunction "2_2") (pintype "passive"))
      (node (ref "Q5") (pin "3") (pinfunction "D_3") (pintype "passive"))
      (node (ref "R19") (pin "2") (pinfunction "2_2") (pintype "passive"))
    )
    (net (code "55") (name "RESET_1") (class "Default")
      (node (ref "C36") (pin "1") (pinfunction "1_1") (pintype "passive"))
      (node (ref "Q5") (pin "2") (pinfunction "S_2") (pintype "passive"))
      (node (ref "R7") (pin "2") (pinfunction "2_2") (pintype "passive"))
      (node (ref "U4") (pin "10") (pinfunction "RSTN_10") (pintype "input"))
    )
    (net (code "56") (name "RESET_IN") (class "Default")
      (node (ref "J1") (pin "1") (pinfunction "1_1") (pintype "passive"))
      (node (ref "Q4") (pin "3") (pinfunction "D_3") (pintype "passive"))
      (node (ref "R2") (pin "2") (pinfunction "2_2") (pintype "passive"))
    )
    (net (code "57") (name "SCK") (class "Default")
      (node (ref "J1") (pin "18") (pinfunction "18_18") (pintype "passive"))
      (node (ref "U$30") (pin "E5") (pinfunction "SCLK_E5") (pintype "bidirectional"))
    )
    (net (code "58") (name "SCL") (class "Default")
      (node (ref "Q1") (pin "2") (pinfunction "S_2") (pintype "passive"))
      (node (ref "R12") (pin "2") (pinfunction "2_2") (pintype "passive"))
      (node (ref "R3") (pin "2") (pinfunction "2_2") (pintype "passive"))
      (node (ref "U$3") (pin "24") (pinfunction "SLAVE_SCL_24") (pintype "bidirectional"))
      (node (ref "U4") (pin "3") (pinfunction "P0.8_3") (pintype "passive"))
    )
    (net (code "59") (name "SCL_IN") (class "Default")
      (node (ref "J1") (pin "4") (pinfunction "4_4") (pintype "passive"))
      (node (ref "Q1") (pin "3") (pinfunction "D_3") (pintype "passive"))
      (node (ref "R13") (pin "2") (pinfunction "2_2") (pintype "passive"))
    )
    (net (code "60") (name "SDA") (class "Default")
      (node (ref "Q2") (pin "2") (pinfunction "S_2") (pintype "passive"))
      (node (ref "R15") (pin "2") (pinfunction "2_2") (pintype "passive"))
      (node (ref "R4") (pin "2") (pinfunction "2_2") (pintype "passive"))
      (node (ref "U$3") (pin "23") (pinfunction "SLAVE_SDA_23") (pintype "bidirectional"))
      (node (ref "U4") (pin "4") (pinfunction "P0.9_4") (pintype "passive"))
    )
    (net (code "61") (name "SDA_IN") (class "Default")
      (node (ref "J1") (pin "3") (pinfunction "3_3") (pintype "passive"))
      (node (ref "Q2") (pin "3") (pinfunction "D_3") (pintype "passive"))
      (node (ref "R16") (pin "2") (pinfunction "2_2") (pintype "passive"))
    )
    (net (code "62") (name "SDI") (class "Default")
      (node (ref "U$39") (pin "2") (pinfunction "SDI/SDA_2") (pintype "bidirectional"))
      (node (ref "U4") (pin "36") (pinfunction "P0.5_36") (pintype "bidirectional"))
    )
    (net (code "63") (name "SDO") (class "Default")
      (node (ref "U$39") (pin "1") (pinfunction "SDO/ADDR_1") (pintype "bidirectional"))
      (node (ref "U4") (pin "37") (pinfunction "P0.4_37") (pintype "bidirectional"))
    )
    (net (code "64") (name "SEN_CS") (class "Default")
      (node (ref "U$39") (pin "10") (pinfunction "NCS_10") (pintype "bidirectional"))
      (node (ref "U4") (pin "11") (pinfunction "P0.0_11") (pintype "passive"))
    )
    (net (code "65") (name "SEN_SCK") (class "Default")
      (node (ref "U$39") (pin "12") (pinfunction "SCLK/SCL_12") (pintype "bidirectional"))
      (node (ref "U4") (pin "35") (pinfunction "P0.6_35") (pintype "bidirectional"))
    )
    (net (code "66") (name "S_SCL") (class "Default")
      (node (ref "D2") (pin "2") (pinfunction "2_2") (pintype "bidirectional"))
      (node (ref "J2") (pin "16") (pinfunction "16_16") (pintype "passive"))
      (node (ref "JP1") (pin "4") (pinfunction "P$4_4") (pintype "bidirectional"))
      (node (ref "R5") (pin "2") (pinfunction "2_2") (pintype "passive"))
      (node (ref "U$3") (pin "14") (pinfunction "SENSOR_SCL_14") (pintype "bidirectional"))
    )
    (net (code "67") (name "S_SDA") (class "Default")
      (node (ref "D1") (pin "2") (pinfunction "2_2") (pintype "bidirectional"))
      (node (ref "J2") (pin "18") (pinfunction "18_18") (pintype "passive"))
      (node (ref "JP1") (pin "3") (pinfunction "P$3_3") (pintype "bidirectional"))
      (node (ref "R6") (pin "2") (pinfunction "2_2") (pintype "passive"))
      (node (ref "U$3") (pin "13") (pinfunction "SENSOR_SDA_13") (pintype "bidirectional"))
    )
    (net (code "68") (name "VBAT") (class "Default")
      (node (ref "C10") (pin "1") (pinfunction "1_1") (pintype "passive"))
      (node (ref "C19") (pin "1") (pinfunction "1_1") (pintype "passive"))
      (node (ref "J2") (pin "15") (pinfunction "15_15") (pintype "passive"))
      (node (ref "L1") (pin "1") (pinfunction "1_1") (pintype "passive"))
      (node (ref "U$6") (pin "1") (pinfunction "VIN_1") (pintype "bidirectional"))
      (node (ref "U$6") (pin "3") (pinfunction "EN_3") (pintype "bidirectional"))
      (node (ref "U1") (pin "5") (pinfunction "IN_5") (pintype "input"))
      (node (ref "U1") (pin "6") (pinfunction "EN_6") (pintype "bidirectional"))
    )
    (net (code "69") (name "VSENSE") (class "Default")
      (node (ref "C27") (pin "1") (pinfunction "1_1") (pintype "passive"))
      (node (ref "C38") (pin "1") (pinfunction "1_1") (pintype "passive"))
      (node (ref "C39") (pin "1") (pinfunction "1_1") (pintype "passive"))
      (node (ref "C40") (pin "1") (pinfunction "1_1") (pintype "passive"))
      (node (ref "C41") (pin "1") (pinfunction "1_1") (pintype "passive"))
      (node (ref "C42") (pin "1") (pinfunction "1_1") (pintype "passive"))
      (node (ref "C48") (pin "1") (pinfunction "1_1") (pintype "passive"))
      (node (ref "C9") (pin "1") (pinfunction "1_1") (pintype "passive"))
      (node (ref "D3") (pin "A") (pinfunction "A_A") (pintype "passive"))
      (node (ref "D4") (pin "A") (pinfunction "A_A") (pintype "passive"))
      (node (ref "J2") (pin "17") (pinfunction "17_17") (pintype "passive"))
      (node (ref "J2") (pin "19") (pinfunction "19_19") (pintype "passive"))
      (node (ref "JP1") (pin "1") (pinfunction "P$1_1") (pintype "bidirectional"))
      (node (ref "LED1") (pin "3") (pinfunction "A_3") (pintype "passive"))
      (node (ref "U1") (pin "1") (pinfunction "OUT_1") (pintype "output"))
      (node (ref "U4") (pin "18") (pinfunction "VLED_18") (pintype "input"))
      (node (ref "U6") (pin "10") (pinfunction "V+_10") (pintype "power_in"))
    )
    (net (code "70") (name "W_MFIO") (class "Default")
      (node (ref "J1") (pin "10") (pinfunction "10_10") (pintype "passive"))
      (node (ref "R20") (pin "1") (pinfunction "1_1") (pintype "passive"))
      (node (ref "U4") (pin "12") (pinfunction "P0.1_12") (pintype "passive"))
    )
    (net (code "71") (name "unconnected-(J1-Pad7)") (class "Default")
      (node (ref "J1") (pin "7") (pinfunction "7_7") (pintype "passive"))
    )
    (net (code "72") (name "unconnected-(J1-Pad12)") (class "Default")
      (node (ref "J1") (pin "12") (pinfunction "12_12") (pintype "passive"))
    )
    (net (code "73") (name "unconnected-(J1-Pad13)") (class "Default")
      (node (ref "J1") (pin "13") (pinfunction "13_13") (pintype "passive"))
    )
    (net (code "74") (name "unconnected-(J1-Pad16)") (class "Default")
      (node (ref "J1") (pin "16") (pinfunction "16_16") (pintype "passive"))
    )
    (net (code "75") (name "unconnected-(J2-Pad3)") (class "Default")
      (node (ref "J2") (pin "3") (pinfunction "3_3") (pintype "passive"))
    )
    (net (code "76") (name "unconnected-(J2-Pad4)") (class "Default")
      (node (ref "J2") (pin "4") (pinfunction "4_4") (pintype "passive"))
    )
    (net (code "77") (name "unconnected-(J2-Pad5)") (class "Default")
      (node (ref "J2") (pin "5") (pinfunction "5_5") (pintype "passive"))
    )
    (net (code "78") (name "unconnected-(J2-Pad6)") (class "Default")
      (node (ref "J2") (pin "6") (pinfunction "6_6") (pintype "passive"))
    )
    (net (code "79") (name "unconnected-(J2-Pad7)") (class "Default")
      (node (ref "J2") (pin "7") (pinfunction "7_7") (pintype "passive"))
    )
    (net (code "80") (name "unconnected-(J2-Pad8)") (class "Default")
      (node (ref "J2") (pin "8") (pinfunction "8_8") (pintype "passive"))
    )
    (net (code "81") (name "unconnected-(J2-Pad9)") (class "Default")
      (node (ref "J2") (pin "9") (pinfunction "9_9") (pintype "passive"))
    )
    (net (code "82") (name "unconnected-(J2-Pad10)") (class "Default")
      (node (ref "J2") (pin "10") (pinfunction "10_10") (pintype "passive"))
    )
    (net (code "83") (name "unconnected-(J2-Pad11)") (class "Default")
      (node (ref "J2") (pin "11") (pinfunction "11_11") (pintype "passive"))
    )
    (net (code "84") (name "unconnected-(J2-Pad12)") (class "Default")
      (node (ref "J2") (pin "12") (pinfunction "12_12") (pintype "passive"))
    )
    (net (code "85") (name "unconnected-(J2-Pad13)") (class "Default")
      (node (ref "J2") (pin "13") (pinfunction "13_13") (pintype "passive"))
    )
    (net (code "86") (name "unconnected-(U$3-ACCL_INT-Pad19)") (class "Default")
      (node (ref "U$3") (pin "19") (pinfunction "ACCL_INT_19") (pintype "bidirectional"))
    )
    (net (code "87") (name "unconnected-(U$3-D.N.C-Pad2)") (class "Default")
      (node (ref "U$3") (pin "2") (pinfunction "D.N.C_2") (pintype "bidirectional"))
    )
    (net (code "88") (name "unconnected-(U$3-D.N.C-Pad4)") (class "Default")
      (node (ref "U$3") (pin "4") (pinfunction "D.N.C_4") (pintype "bidirectional"))
    )
    (net (code "89") (name "unconnected-(U$3-D.N.C-Pad5)") (class "Default")
      (node (ref "U$3") (pin "5") (pinfunction "D.N.C_5") (pintype "bidirectional"))
    )
    (net (code "90") (name "unconnected-(U$3-D.N.C-Pad16)") (class "Default")
      (node (ref "U$3") (pin "16") (pinfunction "D.N.C_16") (pintype "bidirectional"))
    )
    (net (code "91") (name "unconnected-(U$3-D.N.C-Pad17)") (class "Default")
      (node (ref "U$3") (pin "17") (pinfunction "D.N.C_17") (pintype "bidirectional"))
    )
    (net (code "92") (name "unconnected-(U$3-D.N.C-Pad20)") (class "Default")
      (node (ref "U$3") (pin "20") (pinfunction "D.N.C_20") (pintype "bidirectional"))
    )
    (net (code "93") (name "unconnected-(U$3-D.N.C-Pad21)") (class "Default")
      (node (ref "U$3") (pin "21") (pinfunction "D.N.C_21") (pintype "bidirectional"))
    )
    (net (code "94") (name "unconnected-(U$3-N.C-Pad3)") (class "Default")
      (node (ref "U$3") (pin "3") (pinfunction "N.C_3") (pintype "bidirectional"))
    )
    (net (code "95") (name "unconnected-(U$3-N.C-Pad15)") (class "Default")
      (node (ref "U$3") (pin "15") (pinfunction "N.C_15") (pintype "bidirectional"))
    )
    (net (code "96") (name "unconnected-(U$6-NC-Pad4)") (class "Default")
      (node (ref "U$6") (pin "4") (pinfunction "NC_4") (pintype "bidirectional"))
    )
    (net (code "97") (name "unconnected-(U$29-NC-Pad1)") (class "Default")
      (node (ref "U$29") (pin "1") (pinfunction "NC_1") (pintype "bidirectional"))
    )
    (net (code "98") (name "unconnected-(U$30-AOUT-PadC2)") (class "Default")
      (node (ref "U$30") (pin "C2") (pinfunction "AOUT_C2") (pintype "bidirectional"))
    )
    (net (code "99") (name "unconnected-(U$30-INT2B-PadE2)") (class "Default")
      (node (ref "U$30") (pin "E2") (pinfunction "INT2B_E2") (pintype "bidirectional"))
    )
    (net (code "100") (name "unconnected-(U$39-INT2-Pad6)") (class "Default")
      (node (ref "U$39") (pin "6") (pinfunction "INT2_6") (pintype "bidirectional"))
    )
    (net (code "101") (name "unconnected-(U$39-NC-Pad11)") (class "Default")
      (node (ref "U$39") (pin "11") (pinfunction "NC_11") (pintype "bidirectional"))
    )
    (net (code "102") (name "unconnected-(U4-NC-Pad34)") (class "Default")
      (node (ref "U4") (pin "34") (pinfunction "NC_34") (pintype "passive"))
    )
    (net (code "103") (name "unconnected-(U4-NC_2-Pad14)") (class "Default")
      (node (ref "U4") (pin "14") (pinfunction "NC_2_14") (pintype "passive"))
    )
    (net (code "104") (name "unconnected-(U4-NC_3-Pad15)") (class "Default")
      (node (ref "U4") (pin "15") (pinfunction "NC_3_15") (pintype "passive"))
    )
    (net (code "105") (name "unconnected-(U4-NC_4-Pad16)") (class "Default")
      (node (ref "U4") (pin "16") (pinfunction "NC_4_16") (pintype "passive"))
    )
    (net (code "106") (name "unconnected-(U4-NC_5-Pad17)") (class "Default")
      (node (ref "U4") (pin "17") (pinfunction "NC_5_17") (pintype "passive"))
    )
    (net (code "107") (name "unconnected-(U4-NC_6-Pad27)") (class "Default")
      (node (ref "U4") (pin "27") (pinfunction "NC_6_27") (pintype "passive"))
    )
    (net (code "108") (name "unconnected-(U4-PD1_IN-Pad1)") (class "Default")
      (node (ref "U4") (pin "1") (pinfunction "PD1_IN_1") (pintype "input"))
    )
    (net (code "109") (name "unconnected-(U6-COM3-Pad4)") (class "Default")
      (node (ref "U6") (pin "4") (pinfunction "COM3_4") (pintype "bidirectional"))
    )
    (net (code "110") (name "unconnected-(U6-COM4-Pad8)") (class "Default")
      (node (ref "U6") (pin "8") (pinfunction "COM4_8") (pintype "bidirectional"))
    )
    (net (code "111") (name "unconnected-(U6-NC3-Pad5)") (class "Default")
      (node (ref "U6") (pin "5") (pinfunction "NC3_5") (pintype "bidirectional"))
    )
    (net (code "112") (name "unconnected-(U6-NC4-Pad9)") (class "Default")
      (node (ref "U6") (pin "9") (pinfunction "NC4_9") (pintype "bidirectional"))
    )
    (net (code "113") (name "unconnected-(U6-NO3-Pad3)") (class "Default")
      (node (ref "U6") (pin "3") (pinfunction "NO3_3") (pintype "bidirectional"))
    )
    (net (code "114") (name "unconnected-(U6-NO4-Pad7)") (class "Default")
      (node (ref "U6") (pin "7") (pinfunction "NO4_7") (pintype "bidirectional"))
    )
  )
)
